# conv.net
KiCad netlist of a schematic drawn in EAGLE
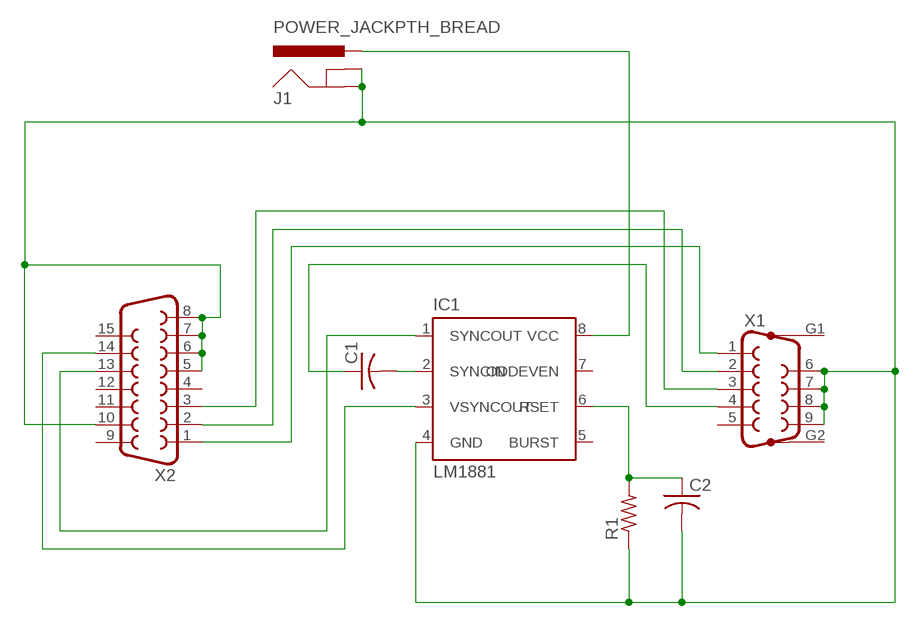
[diagram p0: schematic, sheet 1]

(export (version "E")
  (design (tool "Eeschema 10.0.6"))
  (components
    (comp (ref "C1")
      (value "C-US025-040X050")
      (footprint "eagle-import:C025-040X050")
      (libsource (lib "eagle-import") (part "C-US025-040X050"))
    )
    (comp (ref "C2")
      (value "C-US025-040X050")
      (footprint "eagle-import:C025-040X050")
      (libsource (lib "eagle-import") (part "C-US025-040X050"))
    )
    (comp (ref "IC1")
      (value "LM1881")
      (footprint "eagle-import:DIL08")
      (libsource (lib "eagle-import") (part "LM1881"))
    )
    (comp (ref "J1")
      (value "POWER_JACKPTH_BREAD")
      (footprint "eagle-import:POWER_JACK_PTH_BREAD")
      (libsource (lib "eagle-import") (part "POWER_JACKPTH_BREAD"))
    )
    (comp (ref "R1")
      (value "R-US_0207/10")
      (footprint "eagle-import:0207_10")
      (libsource (lib "eagle-import") (part "R-US_0207/10"))
    )
    (comp (ref "X1")
      (value "F09HP")
      (footprint "eagle-import:F09HP")
      (libsource (lib "eagle-import") (part "F09HP"))
    )
    (comp (ref "X2")
      (value "F15HDH")
      (footprint "eagle-import:HDF15H")
      (libsource (lib "eagle-import") (part "F15HDH"))
    )
  )
  (nets
    (net (code "1") (name "Net-(C1-Pad1)") (class "Default")
      (node (ref "C1") (pin "1") (pinfunction "1_1") (pintype "passive"))
      (node (ref "X1") (pin "4") (pinfunction "4_4") (pintype "passive"))
    )
    (net (code "2") (name "Net-(IC1-GND)") (class "Default")
      (node (ref "C2") (pin "2") (pinfunction "2_2") (pintype "passive"))
      (node (ref "IC1") (pin "4") (pinfunction "GND_4") (pintype "power_in"))
      (node (ref "J1") (pin "GND") (pinfunction "GND_GND") (pintype "bidirectional"))
      (node (ref "J1") (pin "GNDBREAK") (pinfunction "GNDBREAK_GNDBREAK") (pintype "bidirectional"))
      (node (ref "R1") (pin "1") (pinfunction "1_1") (pintype "passive"))
      (node (ref "X1") (pin "6") (pinfunction "6_6") (pintype "passive"))
      (node (ref "X1") (pin "7") (pinfunction "7_7") (pintype "passive"))
      (node (ref "X1") (pin "8") (pinfunction "8_8") (pintype "passive"))
      (node (ref "X1") (pin "9") (pinfunction "9_9") (pintype "passive"))
      (node (ref "X2") (pin "10") (pinfunction "10_10") (pintype "passive"))
      (node (ref "X2") (pin "5") (pinfunction "5_5") (pintype "passive"))
      (node (ref "X2") (pin "6") (pinfunction "6_6") (pintype "passive"))
      (node (ref "X2") (pin "7") (pinfunction "7_7") (pintype "passive"))
      (node (ref "X2") (pin "8") (pinfunction "8_8") (pintype "passive"))
    )
    (net (code "3") (name "Net-(IC1-RSET)") (class "Default")
      (node (ref "C2") (pin "1") (pinfunction "1_1") (pintype "passive"))
      (node (ref "IC1") (pin "6") (pinfunction "RSET_6") (pintype "output"))
      (node (ref "R1") (pin "2") (pinfunction "2_2") (pintype "passive"))
    )
    (net (code "4") (name "Net-(IC1-SYNCIN)") (class "Default")
      (node (ref "C1") (pin "2") (pinfunction "2_2") (pintype "passive"))
      (node (ref "IC1") (pin "2") (pinfunction "SYNCIN_2") (pintype "input"))
    )
    (net (code "5") (name "Net-(IC1-SYNCOUT)") (class "Default")
      (node (ref "IC1") (pin "1") (pinfunction "SYNCOUT_1") (pintype "output"))
      (node (ref "X2") (pin "13") (pinfunction "13_13") (pintype "passive"))
    )
    (net (code "6") (name "Net-(IC1-VCC)") (class "Default")
      (node (ref "IC1") (pin "8") (pinfunction "VCC_8") (pintype "power_in"))
      (node (ref "J1") (pin "PWR") (pinfunction "PWR_PWR") (pintype "bidirectional"))
    )
    (net (code "7") (name "Net-(IC1-VSYNCOUT)") (class "Default")
      (node (ref "IC1") (pin "3") (pinfunction "VSYNCOUT_3") (pintype "output"))
      (node (ref "X2") (pin "14") (pinfunction "14_14") (pintype "passive"))
    )
    (net (code "8") (name "Net-(X1-Pad1)") (class "Default")
      (node (ref "X1") (pin "1") (pinfunction "1_1") (pintype "passive"))
      (node (ref "X2") (pin "1") (pinfunction "1_1") (pintype "passive"))
    )
    (net (code "9") (name "Net-(X1-Pad2)") (class "Default")
      (node (ref "X1") (pin "2") (pinfunction "2_2") (pintype "passive"))
      (node (ref "X2") (pin "2") (pinfunction "2_2") (pintype "passive"))
    )
    (net (code "10") (name "Net-(X1-Pad3)") (class "Default")
      (node (ref "X1") (pin "3") (pinfunction "3_3") (pintype "passive"))
      (node (ref "X2") (pin "3") (pinfunction "3_3") (pintype "passive"))
    )
    (net (code "11") (name "unconnected-(IC1-BURST-Pad5)") (class "Default")
      (node (ref "IC1") (pin "5") (pinfunction "BURST_5") (pintype "output"))
    )
    (net (code "12") (name "unconnected-(IC1-ODDEVEN-Pad7)") (class "Default")
      (node (ref "IC1") (pin "7") (pinfunction "ODDEVEN_7") (pintype "output"))
    )
    (net (code "13") (name "unconnected-(X1-Pad5)") (class "Default")
      (node (ref "X1") (pin "5") (pinfunction "5_5") (pintype "passive"))
    )
    (net (code "14") (name "unconnected-(X1-PadG1)") (class "Default")
      (node (ref "X1") (pin "G1") (pinfunction "G1_G1") (pintype "passive"))
    )
    (net (code "15") (name "unconnected-(X1-PadG2)") (class "Default")
      (node (ref "X1") (pin "G2") (pinfunction "G2_G2") (pintype "passive"))
    )
    (net (code "16") (name "unconnected-(X2-Pad4)") (class "Default")
      (node (ref "X2") (pin "4") (pinfunction "4_4") (pintype "passive"))
    )
    (net (code "17") (name "unconnected-(X2-Pad9)") (class "Default")
      (node (ref "X2") (pin "9") (pinfunction "9_9") (pintype "passive"))
    )
    (net (code "18") (name "unconnected-(X2-Pad11)") (class "Default")
      (node (ref "X2") (pin "11") (pinfunction "11_11") (pintype "passive"))
    )
    (net (code "19") (name "unconnected-(X2-Pad12)") (class "Default")
      (node (ref "X2") (pin "12") (pinfunction "12_12") (pintype "passive"))
    )
    (net (code "20") (name "unconnected-(X2-Pad15)") (class "Default")
      (node (ref "X2") (pin "15") (pinfunction "15_15") (pintype "passive"))
    )
  )
)
